# PCIe_to_SATA.net
KiCad netlist of a schematic drawn in Altium Designer
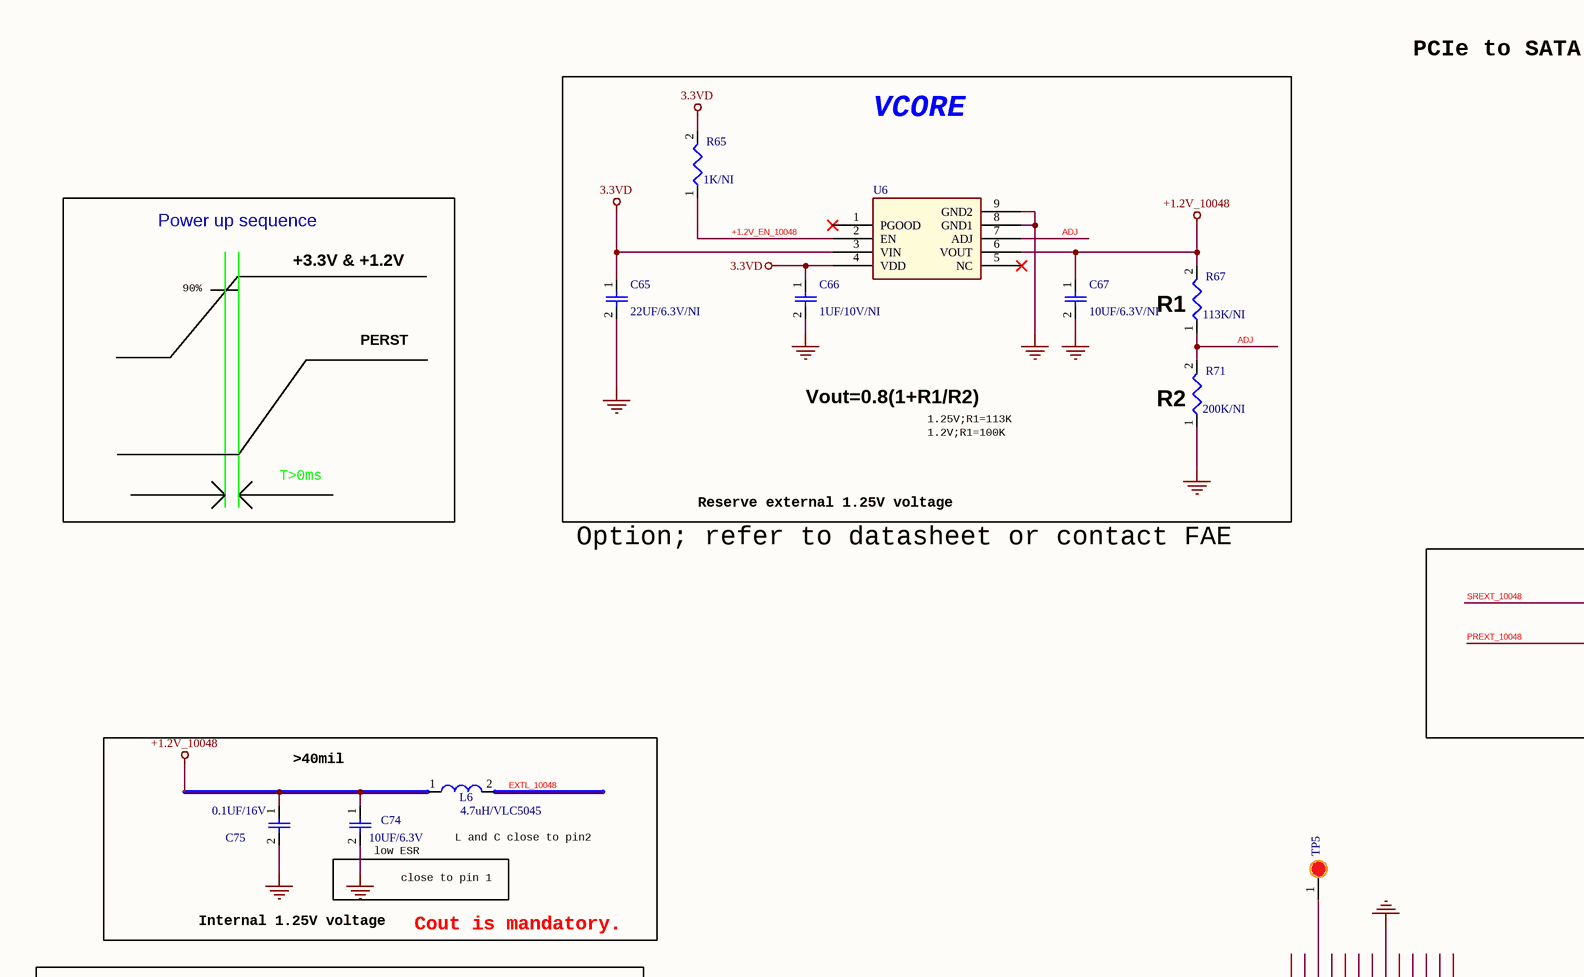
[diagram p0: PCIe to SATA.SchDoc, top left]
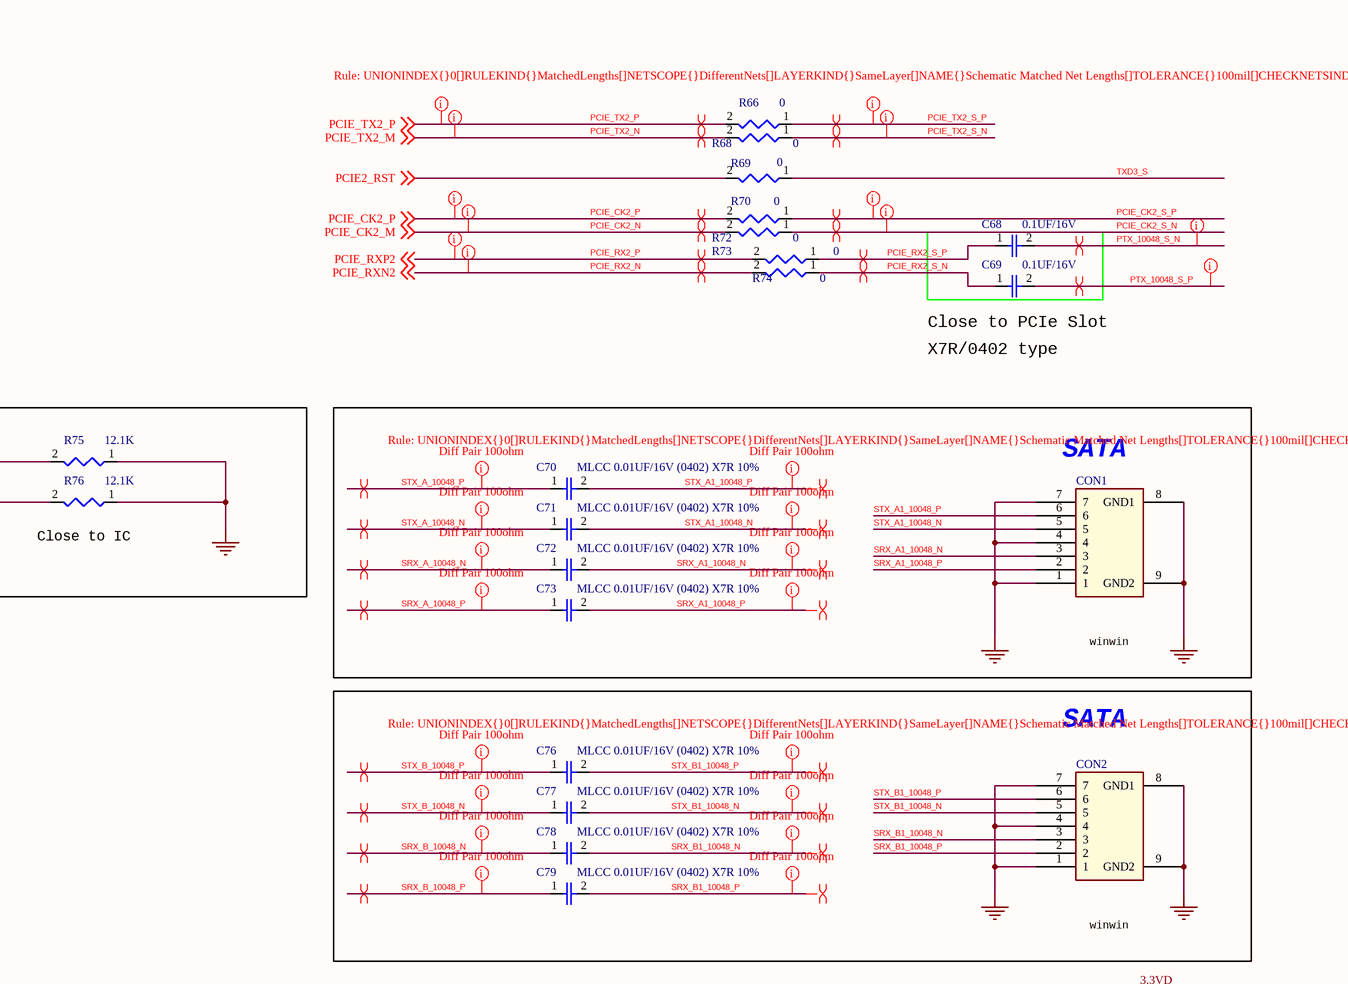
[diagram p1: PCIe to SATA.SchDoc, top right]
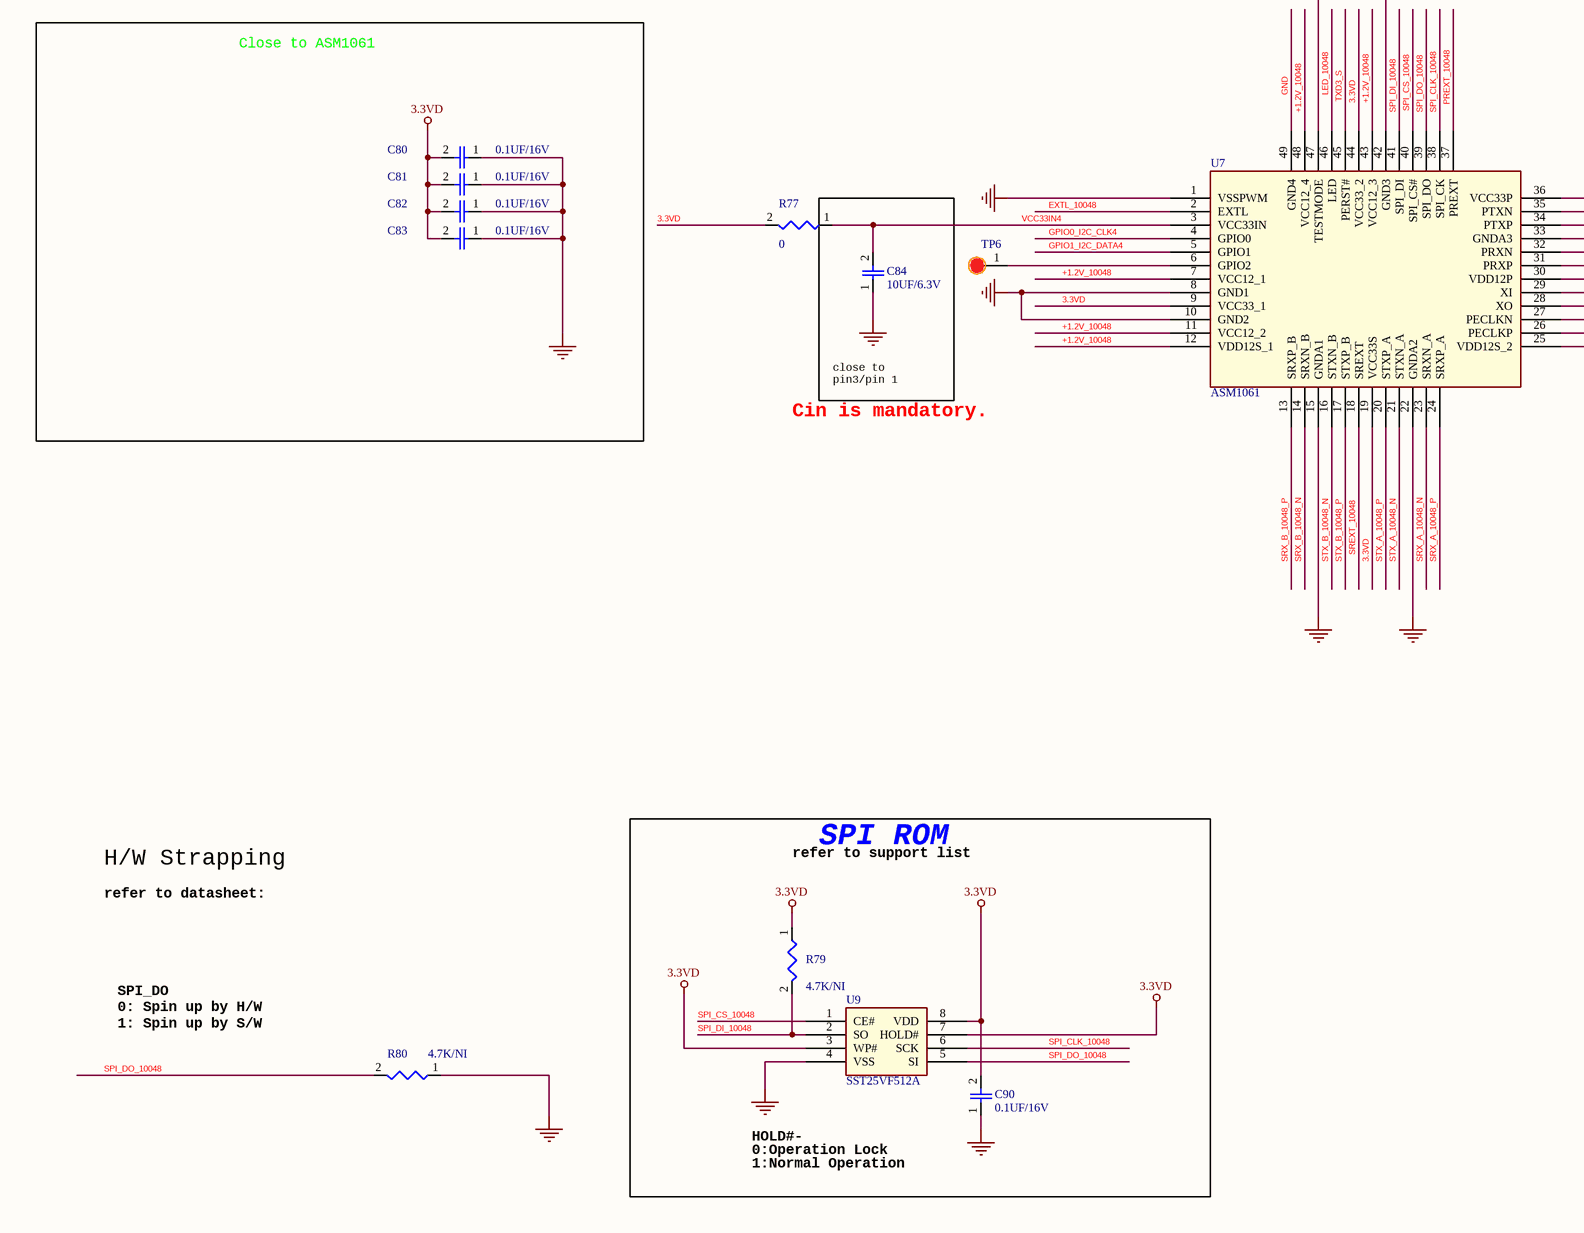
[diagram p2: PCIe to SATA.SchDoc, bottom left]
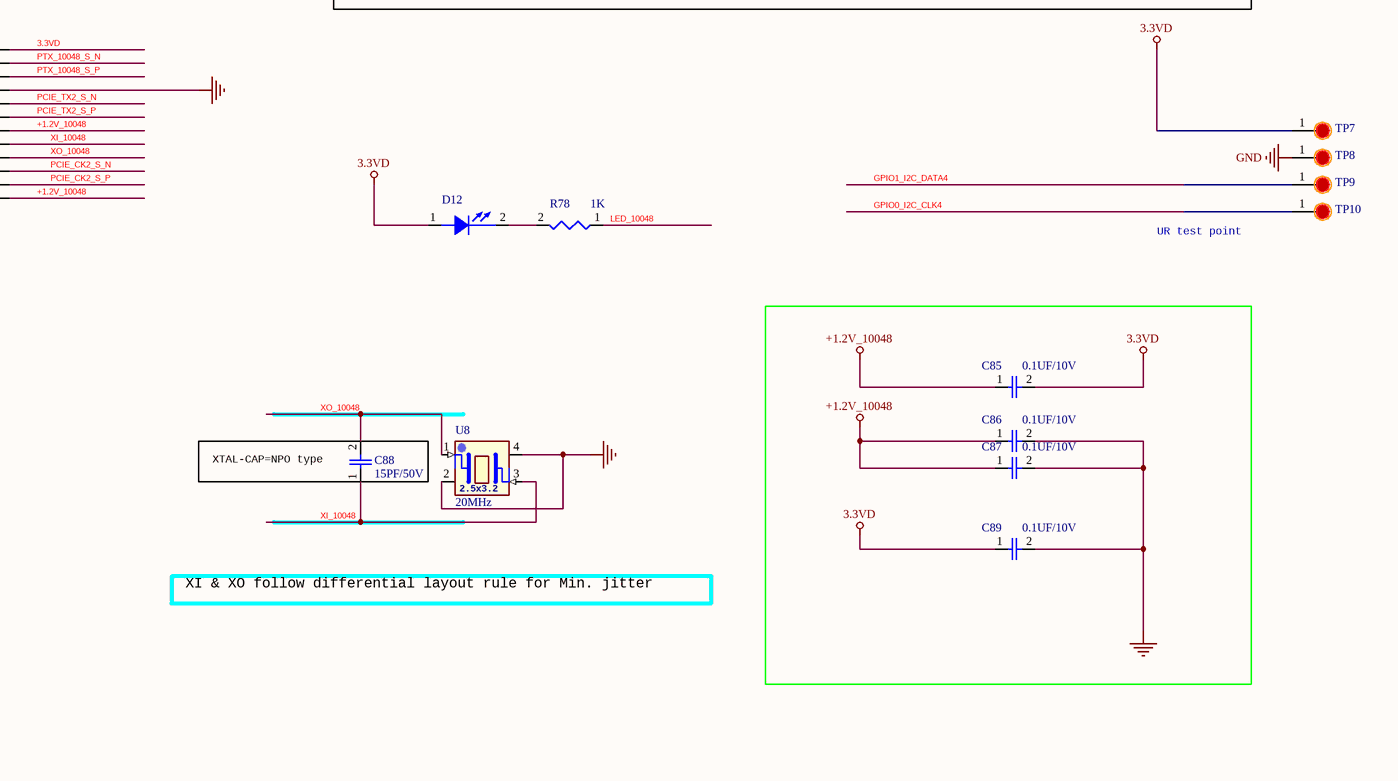
[diagram p3: PCIe to SATA.SchDoc, bottom right]

(export (version "E")
  (design (tool "Eeschema 10.0.6"))
  (components
    (comp (ref "C65") (value "22UF/6.3V/NI") (footprint "0805-C") (libsource (lib "OOLITEV8") (part "CAP")))
    (comp (ref "C66") (value "1UF/10V/NI") (footprint "0402-C") (libsource (lib "OOLITEV8") (part "CAP")))
    (comp (ref "C67") (value "10UF/6.3V/NI") (footprint "0603-C") (libsource (lib "OOLITEV8") (part "CAP")))
    (comp (ref "C68") (value "0.1UF/16V") (footprint "0402-C") (libsource (lib "OOLITEV8") (part "CAP")))
    (comp (ref "C69") (value "0.1UF/16V") (footprint "0402-C") (libsource (lib "OOLITEV8") (part "CAP")))
    (comp (ref "C70")
      (value "MLCC 0.01UF/16V (0402) X7R 10%")
      (footprint "0402-C")
      (libsource (lib "OOLITEV8") (part "CAP"))
    )
    (comp (ref "C71")
      (value "MLCC 0.01UF/16V (0402) X7R 10%")
      (footprint "0402-C")
      (libsource (lib "OOLITEV8") (part "CAP"))
    )
    (comp (ref "C72")
      (value "MLCC 0.01UF/16V (0402) X7R 10%")
      (footprint "0402-C")
      (libsource (lib "OOLITEV8") (part "CAP"))
    )
    (comp (ref "C73")
      (value "MLCC 0.01UF/16V (0402) X7R 10%")
      (footprint "0402-C")
      (libsource (lib "OOLITEV8") (part "CAP"))
    )
    (comp (ref "C74") (value "10UF/6.3V") (footprint "0603-C") (libsource (lib "OOLITEV8") (part "CAP")))
    (comp (ref "C75") (value "0.1UF/16V") (footprint "0402-C") (libsource (lib "OOLITEV8") (part "CAP")))
    (comp (ref "C76")
      (value "MLCC 0.01UF/16V (0402) X7R 10%")
      (footprint "0402-C")
      (libsource (lib "OOLITEV8") (part "CAP"))
    )
    (comp (ref "C77")
      (value "MLCC 0.01UF/16V (0402) X7R 10%")
      (footprint "0402-C")
      (libsource (lib "OOLITEV8") (part "CAP"))
    )
    (comp (ref "C78")
      (value "MLCC 0.01UF/16V (0402) X7R 10%")
      (footprint "0402-C")
      (libsource (lib "OOLITEV8") (part "CAP"))
    )
    (comp (ref "C79")
      (value "MLCC 0.01UF/16V (0402) X7R 10%")
      (footprint "0402-C")
      (libsource (lib "OOLITEV8") (part "CAP"))
    )
    (comp (ref "C80") (value "0.1UF/16V") (footprint "0402-C") (libsource (lib "OOLITEV8") (part "CAP")))
    (comp (ref "C81") (value "0.1UF/16V") (footprint "0402-C") (libsource (lib "OOLITEV8") (part "CAP")))
    (comp (ref "C82") (value "0.1UF/16V") (footprint "0402-C") (libsource (lib "OOLITEV8") (part "CAP")))
    (comp (ref "C83") (value "0.1UF/16V") (footprint "0402-C") (libsource (lib "OOLITEV8") (part "CAP")))
    (comp (ref "C84") (value "10UF/6.3V") (footprint "0603-C") (libsource (lib "OOLITEV8") (part "CAP")))
    (comp (ref "C85") (value "0.1UF/10V") (footprint "0402-C") (libsource (lib "OOLITEV8") (part "CAP")))
    (comp (ref "C86") (value "0.1UF/10V") (footprint "0402-C") (libsource (lib "OOLITEV8") (part "CAP")))
    (comp (ref "C87") (value "0.1UF/10V") (footprint "0402-C") (libsource (lib "OOLITEV8") (part "CAP")))
    (comp (ref "C88") (value "15PF/50V") (footprint "0402-C") (libsource (lib "OOLITEV8") (part "CAP")))
    (comp (ref "C89") (value "0.1UF/10V") (footprint "0402-C") (libsource (lib "OOLITEV8") (part "CAP")))
    (comp (ref "C90") (value "0.1UF/16V") (footprint "0402-C") (libsource (lib "OOLITEV8") (part "CAP")))
    (comp (ref "CON1")
      (value "SATA_CON_7P_2HOLD")
      (footprint "0678008025")
      (libsource (lib "OOLITEV8") (part "SATA_CON_7P_2HOLD"))
    )
    (comp (ref "CON2")
      (value "SATA_CON_7P_2HOLD")
      (footprint "0678008025")
      (libsource (lib "OOLITEV8") (part "SATA_CON_7P_2HOLD"))
    )
    (comp (ref "D12")
      (value "LED/0603")
      (footprint "LED_0603")
      (libsource (lib "OOLITEV8") (part "LED/0603"))
    )
    (comp (ref "L6")
      (value "4.7uH/VLC5045")
      (footprint "VLC5045")
      (libsource (lib "OOLITEV8") (part "IND/VLC5045"))
    )
    (comp (ref "R65") (value "1K/NI") (footprint "0603-R") (libsource (lib "OOLITEV8") (part "Res")))
    (comp (ref "R66") (value "0") (footprint "0402-R") (libsource (lib "OOLITEV8") (part "Res")))
    (comp (ref "R67") (value "113K/NI") (footprint "0402-R") (libsource (lib "OOLITEV8") (part "Res")))
    (comp (ref "R68") (value "0") (footprint "0402-R") (libsource (lib "OOLITEV8") (part "Res")))
    (comp (ref "R69") (value "0") (footprint "0402-R") (libsource (lib "OOLITEV8") (part "Res")))
    (comp (ref "R70") (value "0") (footprint "0402-R") (libsource (lib "OOLITEV8") (part "Res")))
    (comp (ref "R71") (value "200K/NI") (footprint "0402-R") (libsource (lib "OOLITEV8") (part "Res")))
    (comp (ref "R72") (value "0") (footprint "0402-R") (libsource (lib "OOLITEV8") (part "Res")))
    (comp (ref "R73") (value "0") (footprint "0402-R") (libsource (lib "OOLITEV8") (part "Res")))
    (comp (ref "R74") (value "0") (footprint "0402-R") (libsource (lib "OOLITEV8") (part "Res")))
    (comp (ref "R75") (value "12.1K") (footprint "0402-R") (libsource (lib "OOLITEV8") (part "Res")))
    (comp (ref "R76") (value "12.1K") (footprint "0402-R") (libsource (lib "OOLITEV8") (part "Res")))
    (comp (ref "R77") (value "0") (footprint "0603-R") (libsource (lib "OOLITEV8") (part "Res")))
    (comp (ref "R78") (value "1K") (footprint "0603-R") (libsource (lib "OOLITEV8") (part "Res")))
    (comp (ref "R79") (value "4.7K/NI") (footprint "0603-R") (libsource (lib "OOLITEV8") (part "Res")))
    (comp (ref "R80") (value "4.7K/NI") (footprint "0603-R") (libsource (lib "OOLITEV8") (part "Res")))
    (comp (ref "TP5") (value "TP") (footprint "TP_SMD") (libsource (lib "OOLITEV8") (part "Test Pad")))
    (comp (ref "TP6") (value "TP") (footprint "TP_SMD") (libsource (lib "OOLITEV8") (part "Test Pad")))
    (comp (ref "TP7") (value "TP") (footprint "TP_SMD") (libsource (lib "OOLITEV8") (part "Test Pad")))
    (comp (ref "TP8") (value "TP") (footprint "TP_SMD") (libsource (lib "OOLITEV8") (part "Test Pad")))
    (comp (ref "TP9") (value "TP") (footprint "TP_SMD") (libsource (lib "OOLITEV8") (part "Test Pad")))
    (comp (ref "TP10") (value "TP") (footprint "TP_SMD") (libsource (lib "OOLITEV8") (part "Test Pad")))
    (comp (ref "U6")
      (value "RT9025_25PSP/NI")
      (footprint "SOP-8")
      (libsource (lib "OOLITEV8") (part "RT9025_25PSP"))
    )
    (comp (ref "U7") (value "ASM1061") (footprint "QFN-48") (libsource (lib "OOLITEV8") (part "ASM1061")))
    (comp (ref "U8")
      (value "20MHz")
      (footprint "XTAL_3.2x2.5")
      (libsource (lib "OOLITEV8") (part "XTAL_3.2x2.5"))
    )
    (comp (ref "U9")
      (value "SST25VF512A")
      (footprint "SO-8")
      (description "512 Kbit SPI Serial Flash")
      (libsource (lib "OOLITEV8") (part "SST25VF512A"))
    )
  )
  (nets
    (net (code "1") (name "+1.2V_10048") (class "Default")
      (node (ref "C67") (pin "1") (pinfunction "1_1") (pintype "passive"))
      (node (ref "C74") (pin "1") (pinfunction "1_1") (pintype "passive"))
      (node (ref "C75") (pin "1") (pinfunction "1_1") (pintype "passive"))
      (node (ref "C85") (pin "1") (pinfunction "1_1") (pintype "passive"))
      (node (ref "C86") (pin "1") (pinfunction "1_1") (pintype "passive"))
      (node (ref "C87") (pin "1") (pinfunction "1_1") (pintype "passive"))
      (node (ref "L6") (pin "1") (pinfunction "1_1") (pintype "passive"))
      (node (ref "R67") (pin "2") (pinfunction "2_2") (pintype "passive"))
      (node (ref "U6") (pin "6") (pinfunction "VOUT_6") (pintype "passive"))
      (node (ref "U7") (pin "11") (pinfunction "VCC12_2_11") (pintype "passive"))
      (node (ref "U7") (pin "12") (pinfunction "VDD12S_1_12") (pintype "passive"))
      (node (ref "U7") (pin "25") (pinfunction "VDD12S_2_25") (pintype "passive"))
      (node (ref "U7") (pin "30") (pinfunction "VDD12P_30") (pintype "passive"))
      (node (ref "U7") (pin "43") (pinfunction "VCC12_3_43") (pintype "passive"))
      (node (ref "U7") (pin "48") (pinfunction "VCC12_4_48") (pintype "passive"))
      (node (ref "U7") (pin "7") (pinfunction "VCC12_1_7") (pintype "passive"))
    )
    (net (code "2") (name "/+1.2V_EN_10048") (class "Default")
      (node (ref "R65") (pin "1") (pinfunction "1_1") (pintype "passive"))
      (node (ref "U6") (pin "2") (pinfunction "EN_2") (pintype "passive"))
    )
    (net (code "3") (name "/ADJ") (class "Default")
      (node (ref "R67") (pin "1") (pinfunction "1_1") (pintype "passive"))
      (node (ref "R71") (pin "2") (pinfunction "2_2") (pintype "passive"))
      (node (ref "U6") (pin "7") (pinfunction "ADJ_7") (pintype "passive"))
    )
    (net (code "4") (name "/EXTL_10048") (class "Default")
      (node (ref "L6") (pin "2") (pinfunction "2_2") (pintype "passive"))
      (node (ref "U7") (pin "2") (pinfunction "EXTL_2") (pintype "passive"))
    )
    (net (code "5") (name "/GPIO0_I2C_CLK4") (class "Default")
      (node (ref "TP10") (pin "1") (pinfunction "1_1") (pintype "passive"))
      (node (ref "U7") (pin "4") (pinfunction "GPIO0_4") (pintype "passive"))
    )
    (net (code "6") (name "/GPIO1_I2C_DATA4") (class "Default")
      (node (ref "TP9") (pin "1") (pinfunction "1_1") (pintype "passive"))
      (node (ref "U7") (pin "5") (pinfunction "GPIO1_5") (pintype "passive"))
    )
    (net (code "7") (name "/LED_10048") (class "Default")
      (node (ref "R78") (pin "1") (pinfunction "1_1") (pintype "passive"))
      (node (ref "U7") (pin "46") (pinfunction "LED_46") (pintype "passive"))
    )
    (net (code "8") (name "/PCIE_CK2_S_N") (class "Default")
      (node (ref "R72") (pin "1") (pinfunction "1_1") (pintype "passive"))
      (node (ref "U7") (pin "27") (pinfunction "PECLKN_27") (pintype "passive"))
    )
    (net (code "9") (name "/PCIE_CK2_S_P") (class "Default")
      (node (ref "R70") (pin "1") (pinfunction "1_1") (pintype "passive"))
      (node (ref "U7") (pin "26") (pinfunction "PECLKP_26") (pintype "passive"))
    )
    (net (code "10") (name "/PCIE_RX2_S_N") (class "Default")
      (node (ref "C69") (pin "1") (pinfunction "1_1") (pintype "passive"))
      (node (ref "R74") (pin "1") (pinfunction "1_1") (pintype "passive"))
    )
    (net (code "11") (name "/PCIE_RX2_S_P") (class "Default")
      (node (ref "C68") (pin "1") (pinfunction "1_1") (pintype "passive"))
      (node (ref "R73") (pin "1") (pinfunction "1_1") (pintype "passive"))
    )
    (net (code "12") (name "/PCIE_TX2_S_N") (class "Default")
      (node (ref "R68") (pin "1") (pinfunction "1_1") (pintype "passive"))
      (node (ref "U7") (pin "32") (pinfunction "PRXN_32") (pintype "passive"))
    )
    (net (code "13") (name "/PCIE_TX2_S_P") (class "Default")
      (node (ref "R66") (pin "1") (pinfunction "1_1") (pintype "passive"))
      (node (ref "U7") (pin "31") (pinfunction "PRXP_31") (pintype "passive"))
    )
    (net (code "14") (name "/PREXT_10048") (class "Default")
      (node (ref "R76") (pin "2") (pinfunction "2_2") (pintype "passive"))
      (node (ref "U7") (pin "37") (pinfunction "PREXT_37") (pintype "passive"))
    )
    (net (code "15") (name "/PTX_10048_S_N") (class "Default")
      (node (ref "C68") (pin "2") (pinfunction "2_2") (pintype "passive"))
      (node (ref "U7") (pin "35") (pinfunction "PTXN_35") (pintype "passive"))
    )
    (net (code "16") (name "/PTX_10048_S_P") (class "Default")
      (node (ref "C69") (pin "2") (pinfunction "2_2") (pintype "passive"))
      (node (ref "U7") (pin "34") (pinfunction "PTXP_34") (pintype "passive"))
    )
    (net (code "17") (name "/SPI_CLK_10048") (class "Default")
      (node (ref "U7") (pin "38") (pinfunction "SPI_CK_38") (pintype "passive"))
      (node (ref "U9") (pin "6") (pinfunction "SCK_6") (pintype "passive"))
    )
    (net (code "18") (name "/SPI_CS_10048") (class "Default")
      (node (ref "U7") (pin "40") (pinfunction "SPI_CS#_40") (pintype "passive"))
      (node (ref "U9") (pin "1") (pinfunction "CE#_1") (pintype "passive"))
    )
    (net (code "19") (name "/SPI_DI_10048") (class "Default")
      (node (ref "R79") (pin "2") (pinfunction "2_2") (pintype "passive"))
      (node (ref "U7") (pin "41") (pinfunction "SPI_DI_41") (pintype "passive"))
      (node (ref "U9") (pin "2") (pinfunction "SO_2") (pintype "passive"))
    )
    (net (code "20") (name "/SPI_DO_10048") (class "Default")
      (node (ref "R80") (pin "2") (pinfunction "2_2") (pintype "passive"))
      (node (ref "U7") (pin "39") (pinfunction "SPI_DO_39") (pintype "passive"))
      (node (ref "U9") (pin "5") (pinfunction "SI_5") (pintype "passive"))
    )
    (net (code "21") (name "/SREXT_10048") (class "Default")
      (node (ref "R75") (pin "2") (pinfunction "2_2") (pintype "passive"))
      (node (ref "U7") (pin "18") (pinfunction "SREXT_18") (pintype "passive"))
    )
    (net (code "22") (name "/SRX_A1_10048_N") (class "Default")
      (node (ref "C72") (pin "2") (pinfunction "2_2") (pintype "passive"))
      (node (ref "CON1") (pin "3") (pinfunction "3_3") (pintype "passive"))
    )
    (net (code "23") (name "/SRX_A1_10048_P") (class "Default")
      (node (ref "C73") (pin "2") (pinfunction "2_2") (pintype "passive"))
      (node (ref "CON1") (pin "2") (pinfunction "2_2") (pintype "passive"))
    )
    (net (code "24") (name "/SRX_A_10048_N") (class "Default")
      (node (ref "C72") (pin "1") (pinfunction "1_1") (pintype "passive"))
      (node (ref "U7") (pin "23") (pinfunction "SRXN_A_23") (pintype "passive"))
    )
    (net (code "25") (name "/SRX_A_10048_P") (class "Default")
      (node (ref "C73") (pin "1") (pinfunction "1_1") (pintype "passive"))
      (node (ref "U7") (pin "24") (pinfunction "SRXP_A_24") (pintype "passive"))
    )
    (net (code "26") (name "/SRX_B1_10048_N") (class "Default")
      (node (ref "C78") (pin "2") (pinfunction "2_2") (pintype "passive"))
      (node (ref "CON2") (pin "3") (pinfunction "3_3") (pintype "passive"))
    )
    (net (code "27") (name "/SRX_B1_10048_P") (class "Default")
      (node (ref "C79") (pin "2") (pinfunction "2_2") (pintype "passive"))
      (node (ref "CON2") (pin "2") (pinfunction "2_2") (pintype "passive"))
    )
    (net (code "28") (name "/SRX_B_10048_N") (class "Default")
      (node (ref "C78") (pin "1") (pinfunction "1_1") (pintype "passive"))
      (node (ref "U7") (pin "14") (pinfunction "SRXN_B_14") (pintype "passive"))
    )
    (net (code "29") (name "/SRX_B_10048_P") (class "Default")
      (node (ref "C79") (pin "1") (pinfunction "1_1") (pintype "passive"))
      (node (ref "U7") (pin "13") (pinfunction "SRXP_B_13") (pintype "passive"))
    )
    (net (code "30") (name "/STX_A1_10048_N") (class "Default")
      (node (ref "C71") (pin "2") (pinfunction "2_2") (pintype "passive"))
      (node (ref "CON1") (pin "5") (pinfunction "5_5") (pintype "passive"))
    )
    (net (code "31") (name "/STX_A1_10048_P") (class "Default")
      (node (ref "C70") (pin "2") (pinfunction "2_2") (pintype "passive"))
      (node (ref "CON1") (pin "6") (pinfunction "6_6") (pintype "passive"))
    )
    (net (code "32") (name "/STX_A_10048_N") (class "Default")
      (node (ref "C71") (pin "1") (pinfunction "1_1") (pintype "passive"))
      (node (ref "U7") (pin "21") (pinfunction "STXN_A_21") (pintype "passive"))
    )
    (net (code "33") (name "/STX_A_10048_P") (class "Default")
      (node (ref "C70") (pin "1") (pinfunction "1_1") (pintype "passive"))
      (node (ref "U7") (pin "20") (pinfunction "STXP_A_20") (pintype "passive"))
    )
    (net (code "34") (name "/STX_B1_10048_N") (class "Default")
      (node (ref "C77") (pin "2") (pinfunction "2_2") (pintype "passive"))
      (node (ref "CON2") (pin "5") (pinfunction "5_5") (pintype "passive"))
    )
    (net (code "35") (name "/STX_B1_10048_P") (class "Default")
      (node (ref "C76") (pin "2") (pinfunction "2_2") (pintype "passive"))
      (node (ref "CON2") (pin "6") (pinfunction "6_6") (pintype "passive"))
    )
    (net (code "36") (name "/STX_B_10048_N") (class "Default")
      (node (ref "C77") (pin "1") (pinfunction "1_1") (pintype "passive"))
      (node (ref "U7") (pin "16") (pinfunction "STXN_B_16") (pintype "passive"))
    )
    (net (code "37") (name "/STX_B_10048_P") (class "Default")
      (node (ref "C76") (pin "1") (pinfunction "1_1") (pintype "passive"))
      (node (ref "U7") (pin "17") (pinfunction "STXP_B_17") (pintype "passive"))
    )
    (net (code "38") (name "/TXD3_S") (class "Default")
      (node (ref "R69") (pin "1") (pinfunction "1_1") (pintype "passive"))
      (node (ref "U7") (pin "45") (pinfunction "PERST#_45") (pintype "passive"))
    )
    (net (code "39") (name "/VCC33IN4") (class "Default")
      (node (ref "C84") (pin "2") (pinfunction "2_2") (pintype "passive"))
      (node (ref "R77") (pin "1") (pinfunction "1_1") (pintype "passive"))
      (node (ref "U7") (pin "3") (pinfunction "VCC33IN_3") (pintype "passive"))
    )
    (net (code "40") (name "/XI_10048") (class "Default")
      (node (ref "C88") (pin "1") (pinfunction "1_1") (pintype "passive"))
      (node (ref "U7") (pin "29") (pinfunction "XI_29") (pintype "passive"))
      (node (ref "U8") (pin "3") (pinfunction "X2_3") (pintype "input"))
    )
    (net (code "41") (name "/XO_10048") (class "Default")
      (node (ref "C88") (pin "2") (pinfunction "2_2") (pintype "passive"))
      (node (ref "U7") (pin "28") (pinfunction "XO_28") (pintype "passive"))
      (node (ref "U8") (pin "1") (pinfunction "X1_1") (pintype "input"))
    )
    (net (code "42") (name "3.3VD") (class "Default")
      (node (ref "C65") (pin "1") (pinfunction "1_1") (pintype "passive"))
      (node (ref "C66") (pin "1") (pinfunction "1_1") (pintype "passive"))
      (node (ref "C80") (pin "2") (pinfunction "2_2") (pintype "passive"))
      (node (ref "C81") (pin "2") (pinfunction "2_2") (pintype "passive"))
      (node (ref "C82") (pin "2") (pinfunction "2_2") (pintype "passive"))
      (node (ref "C83") (pin "2") (pinfunction "2_2") (pintype "passive"))
      (node (ref "C85") (pin "2") (pinfunction "2_2") (pintype "passive"))
      (node (ref "C89") (pin "1") (pinfunction "1_1") (pintype "passive"))
      (node (ref "C90") (pin "2") (pinfunction "2_2") (pintype "passive"))
      (node (ref "D12") (pin "1") (pinfunction "ANODE_1") (pintype "passive"))
      (node (ref "R65") (pin "2") (pinfunction "2_2") (pintype "passive"))
      (node (ref "R77") (pin "2") (pinfunction "2_2") (pintype "passive"))
      (node (ref "R79") (pin "1") (pinfunction "1_1") (pintype "passive"))
      (node (ref "TP7") (pin "1") (pinfunction "1_1") (pintype "passive"))
      (node (ref "U6") (pin "3") (pinfunction "VIN_3") (pintype "passive"))
      (node (ref "U6") (pin "4") (pinfunction "VDD_4") (pintype "passive"))
      (node (ref "U7") (pin "19") (pinfunction "VCC33S_19") (pintype "passive"))
      (node (ref "U7") (pin "36") (pinfunction "VCC33P_36") (pintype "passive"))
      (node (ref "U7") (pin "44") (pinfunction "VCC33_2_44") (pintype "passive"))
      (node (ref "U7") (pin "9") (pinfunction "VCC33_1_9") (pintype "passive"))
      (node (ref "U9") (pin "3") (pinfunction "WP#_3") (pintype "passive"))
      (node (ref "U9") (pin "7") (pinfunction "HOLD#_7") (pintype "passive"))
      (node (ref "U9") (pin "8") (pinfunction "VDD_8") (pintype "passive"))
    )
    (net (code "43") (name "GND") (class "Default")
      (node (ref "C65") (pin "2") (pinfunction "2_2") (pintype "passive"))
      (node (ref "C66") (pin "2") (pinfunction "2_2") (pintype "passive"))
      (node (ref "C67") (pin "2") (pinfunction "2_2") (pintype "passive"))
      (node (ref "C74") (pin "2") (pinfunction "2_2") (pintype "passive"))
      (node (ref "C75") (pin "2") (pinfunction "2_2") (pintype "passive"))
      (node (ref "C80") (pin "1") (pinfunction "1_1") (pintype "passive"))
      (node (ref "C81") (pin "1") (pinfunction "1_1") (pintype "passive"))
      (node (ref "C82") (pin "1") (pinfunction "1_1") (pintype "passive"))
      (node (ref "C83") (pin "1") (pinfunction "1_1") (pintype "passive"))
      (node (ref "C84") (pin "1") (pinfunction "1_1") (pintype "passive"))
      (node (ref "C86") (pin "2") (pinfunction "2_2") (pintype "passive"))
      (node (ref "C87") (pin "2") (pinfunction "2_2") (pintype "passive"))
      (node (ref "C89") (pin "2") (pinfunction "2_2") (pintype "passive"))
      (node (ref "C90") (pin "1") (pinfunction "1_1") (pintype "passive"))
      (node (ref "CON1") (pin "1") (pinfunction "1_1") (pintype "passive"))
      (node (ref "CON1") (pin "4") (pinfunction "4_4") (pintype "passive"))
      (node (ref "CON1") (pin "7") (pinfunction "7_7") (pintype "passive"))
      (node (ref "CON1") (pin "8") (pinfunction "GND1_8") (pintype "passive"))
      (node (ref "CON1") (pin "9") (pinfunction "GND2_9") (pintype "passive"))
      (node (ref "CON2") (pin "1") (pinfunction "1_1") (pintype "passive"))
      (node (ref "CON2") (pin "4") (pinfunction "4_4") (pintype "passive"))
      (node (ref "CON2") (pin "7") (pinfunction "7_7") (pintype "passive"))
      (node (ref "CON2") (pin "8") (pinfunction "GND1_8") (pintype "passive"))
      (node (ref "CON2") (pin "9") (pinfunction "GND2_9") (pintype "passive"))
      (node (ref "R71") (pin "1") (pinfunction "1_1") (pintype "passive"))
      (node (ref "R75") (pin "1") (pinfunction "1_1") (pintype "passive"))
      (node (ref "R76") (pin "1") (pinfunction "1_1") (pintype "passive"))
      (node (ref "R80") (pin "1") (pinfunction "1_1") (pintype "passive"))
      (node (ref "TP8") (pin "1") (pinfunction "1_1") (pintype "passive"))
      (node (ref "U6") (pin "8") (pinfunction "GND1_8") (pintype "passive"))
      (node (ref "U6") (pin "9") (pinfunction "GND2_9") (pintype "passive"))
      (node (ref "U7") (pin "1") (pinfunction "VSSPWM_1") (pintype "passive"))
      (node (ref "U7") (pin "10") (pinfunction "GND2_10") (pintype "passive"))
      (node (ref "U7") (pin "15") (pinfunction "GNDA1_15") (pintype "passive"))
      (node (ref "U7") (pin "22") (pinfunction "GNDA2_22") (pintype "passive"))
      (node (ref "U7") (pin "33") (pinfunction "GNDA3_33") (pintype "passive"))
      (node (ref "U7") (pin "42") (pinfunction "GND3_42") (pintype "passive"))
      (node (ref "U7") (pin "49") (pinfunction "GND4_49") (pintype "passive"))
      (node (ref "U7") (pin "8") (pinfunction "GND1_8") (pintype "passive"))
      (node (ref "U8") (pin "2") (pinfunction "NC_2") (pintype "passive"))
      (node (ref "U8") (pin "4") (pinfunction "NC_4") (pintype "passive"))
      (node (ref "U9") (pin "4") (pinfunction "VSS_4") (pintype "passive"))
    )
    (net (code "44") (name "Net-(D12-CATHODE)") (class "Default")
      (node (ref "D12") (pin "2") (pinfunction "CATHODE_2") (pintype "passive"))
      (node (ref "R78") (pin "2") (pinfunction "2_2") (pintype "passive"))
    )
    (net (code "45") (name "Net-(U7-GPIO2)") (class "Default")
      (node (ref "TP6") (pin "1") (pinfunction "1_1") (pintype "passive"))
      (node (ref "U7") (pin "6") (pinfunction "GPIO2_6") (pintype "passive"))
    )
    (net (code "46") (name "Net-(U7-TESTMODE)") (class "Default")
      (node (ref "TP5") (pin "1") (pinfunction "1_1") (pintype "passive"))
      (node (ref "U7") (pin "47") (pinfunction "TESTMODE_47") (pintype "passive"))
    )
    (net (code "47") (name "PCIE2_RST") (class "Default")
      (node (ref "R69") (pin "2") (pinfunction "2_2") (pintype "passive"))
    )
    (net (code "48") (name "PCIE_CK2_M") (class "Default")
      (node (ref "R72") (pin "2") (pinfunction "2_2") (pintype "passive"))
    )
    (net (code "49") (name "PCIE_CK2_P") (class "Default")
      (node (ref "R70") (pin "2") (pinfunction "2_2") (pintype "passive"))
    )
    (net (code "50") (name "PCIE_RXN2") (class "Default")
      (node (ref "R74") (pin "2") (pinfunction "2_2") (pintype "passive"))
    )
    (net (code "51") (name "PCIE_RXP2") (class "Default")
      (node (ref "R73") (pin "2") (pinfunction "2_2") (pintype "passive"))
    )
    (net (code "52") (name "PCIE_TX2_M") (class "Default")
      (node (ref "R68") (pin "2") (pinfunction "2_2") (pintype "passive"))
    )
    (net (code "53") (name "PCIE_TX2_P") (class "Default")
      (node (ref "R66") (pin "2") (pinfunction "2_2") (pintype "passive"))
    )
    (net (code "54") (name "unconnected-(U6-NC-Pad5)") (class "Default")
      (node (ref "U6") (pin "5") (pinfunction "NC_5") (pintype "passive+no_connect"))
    )
    (net (code "55") (name "unconnected-(U6-PGOOD-Pad1)") (class "Default")
      (node (ref "U6") (pin "1") (pinfunction "PGOOD_1") (pintype "passive+no_connect"))
    )
  )
)
